# 3sensor.net
KiCad netlist of a schematic drawn in EAGLE
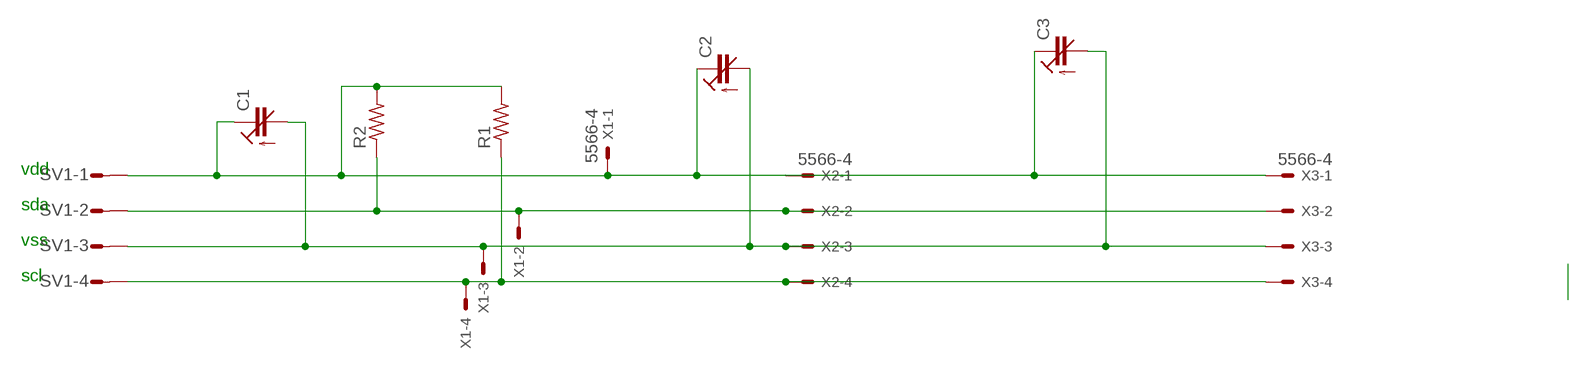
[diagram p0: schematic, sheet 1]

(export (version "E")
  (design (tool "Eeschema 10.0.6"))
  (components
    (comp (ref "C1")
      (value "C-TRIMM3008")
      (footprint "eagle-import:3008")
      (libsource (lib "eagle-import") (part "C-TRIMM3008"))
    )
    (comp (ref "C2")
      (value "C-TRIMM3008")
      (footprint "eagle-import:3008")
      (libsource (lib "eagle-import") (part "C-TRIMM3008"))
    )
    (comp (ref "C3")
      (value "C-TRIMM3008")
      (footprint "eagle-import:3008")
      (libsource (lib "eagle-import") (part "C-TRIMM3008"))
    )
    (comp (ref "R1")
      (value "R-US_0207/12")
      (footprint "eagle-import:0207_12")
      (libsource (lib "eagle-import") (part "R-US_0207/12"))
    )
    (comp (ref "R2")
      (value "R-US_0207/12")
      (footprint "eagle-import:0207_12")
      (libsource (lib "eagle-import") (part "R-US_0207/12"))
    )
    (comp (ref "SV1")
      (value "L04P")
      (footprint "eagle-import:L04P")
      (libsource (lib "eagle-import") (part "L04P"))
    )
    (comp (ref "X1")
      (value "5566-4")
      (footprint "eagle-import:5566-4")
      (libsource (lib "eagle-import") (part "5566-4"))
    )
    (comp (ref "X2")
      (value "5566-4")
      (footprint "eagle-import:5566-4")
      (libsource (lib "eagle-import") (part "5566-4"))
    )
    (comp (ref "X3")
      (value "5566-4")
      (footprint "eagle-import:5566-4")
      (libsource (lib "eagle-import") (part "5566-4"))
    )
  )
  (nets
    (net (code "1") (name "Net-(C1-A)") (class "Default")
      (node (ref "C1") (pin "-") (pinfunction "A_-") (pintype "passive"))
      (node (ref "C2") (pin "-") (pinfunction "A_-") (pintype "passive"))
      (node (ref "C3") (pin "-") (pinfunction "A_-") (pintype "passive"))
      (node (ref "SV1") (pin "3") (pinfunction "S_3") (pintype "passive"))
      (node (ref "X1") (pin "3") (pinfunction "S_3") (pintype "passive"))
      (node (ref "X2") (pin "3") (pinfunction "S_3") (pintype "passive"))
      (node (ref "X3") (pin "3") (pinfunction "S_3") (pintype "passive"))
    )
    (net (code "2") (name "Net-(C1-E)") (class "Default")
      (node (ref "C1") (pin "+") (pinfunction "E_+") (pintype "passive"))
      (node (ref "C2") (pin "+") (pinfunction "E_+") (pintype "passive"))
      (node (ref "C3") (pin "+") (pinfunction "E_+") (pintype "passive"))
      (node (ref "R1") (pin "2") (pinfunction "2_2") (pintype "passive"))
      (node (ref "R2") (pin "2") (pinfunction "2_2") (pintype "passive"))
      (node (ref "SV1") (pin "1") (pinfunction "S_1") (pintype "passive"))
      (node (ref "X1") (pin "1") (pinfunction "S_1") (pintype "passive"))
      (node (ref "X2") (pin "1") (pinfunction "S_1") (pintype "passive"))
      (node (ref "X3") (pin "1") (pinfunction "S_1") (pintype "passive"))
    )
    (net (code "3") (name "Net-(SV1B-S)") (class "Default")
      (node (ref "R2") (pin "1") (pinfunction "1_1") (pintype "passive"))
      (node (ref "SV1") (pin "2") (pinfunction "S_2") (pintype "passive"))
      (node (ref "X1") (pin "2") (pinfunction "S_2") (pintype "passive"))
      (node (ref "X2") (pin "2") (pinfunction "S_2") (pintype "passive"))
      (node (ref "X3") (pin "2") (pinfunction "S_2") (pintype "passive"))
    )
    (net (code "4") (name "Net-(SV1D-S)") (class "Default")
      (node (ref "R1") (pin "1") (pinfunction "1_1") (pintype "passive"))
      (node (ref "SV1") (pin "4") (pinfunction "S_4") (pintype "passive"))
      (node (ref "X1") (pin "4") (pinfunction "S_4") (pintype "passive"))
      (node (ref "X2") (pin "4") (pinfunction "S_4") (pintype "passive"))
      (node (ref "X3") (pin "4") (pinfunction "S_4") (pintype "passive"))
    )
  )
)
